# R1075X.net
KiCad netlist of a schematic drawn in EAGLE
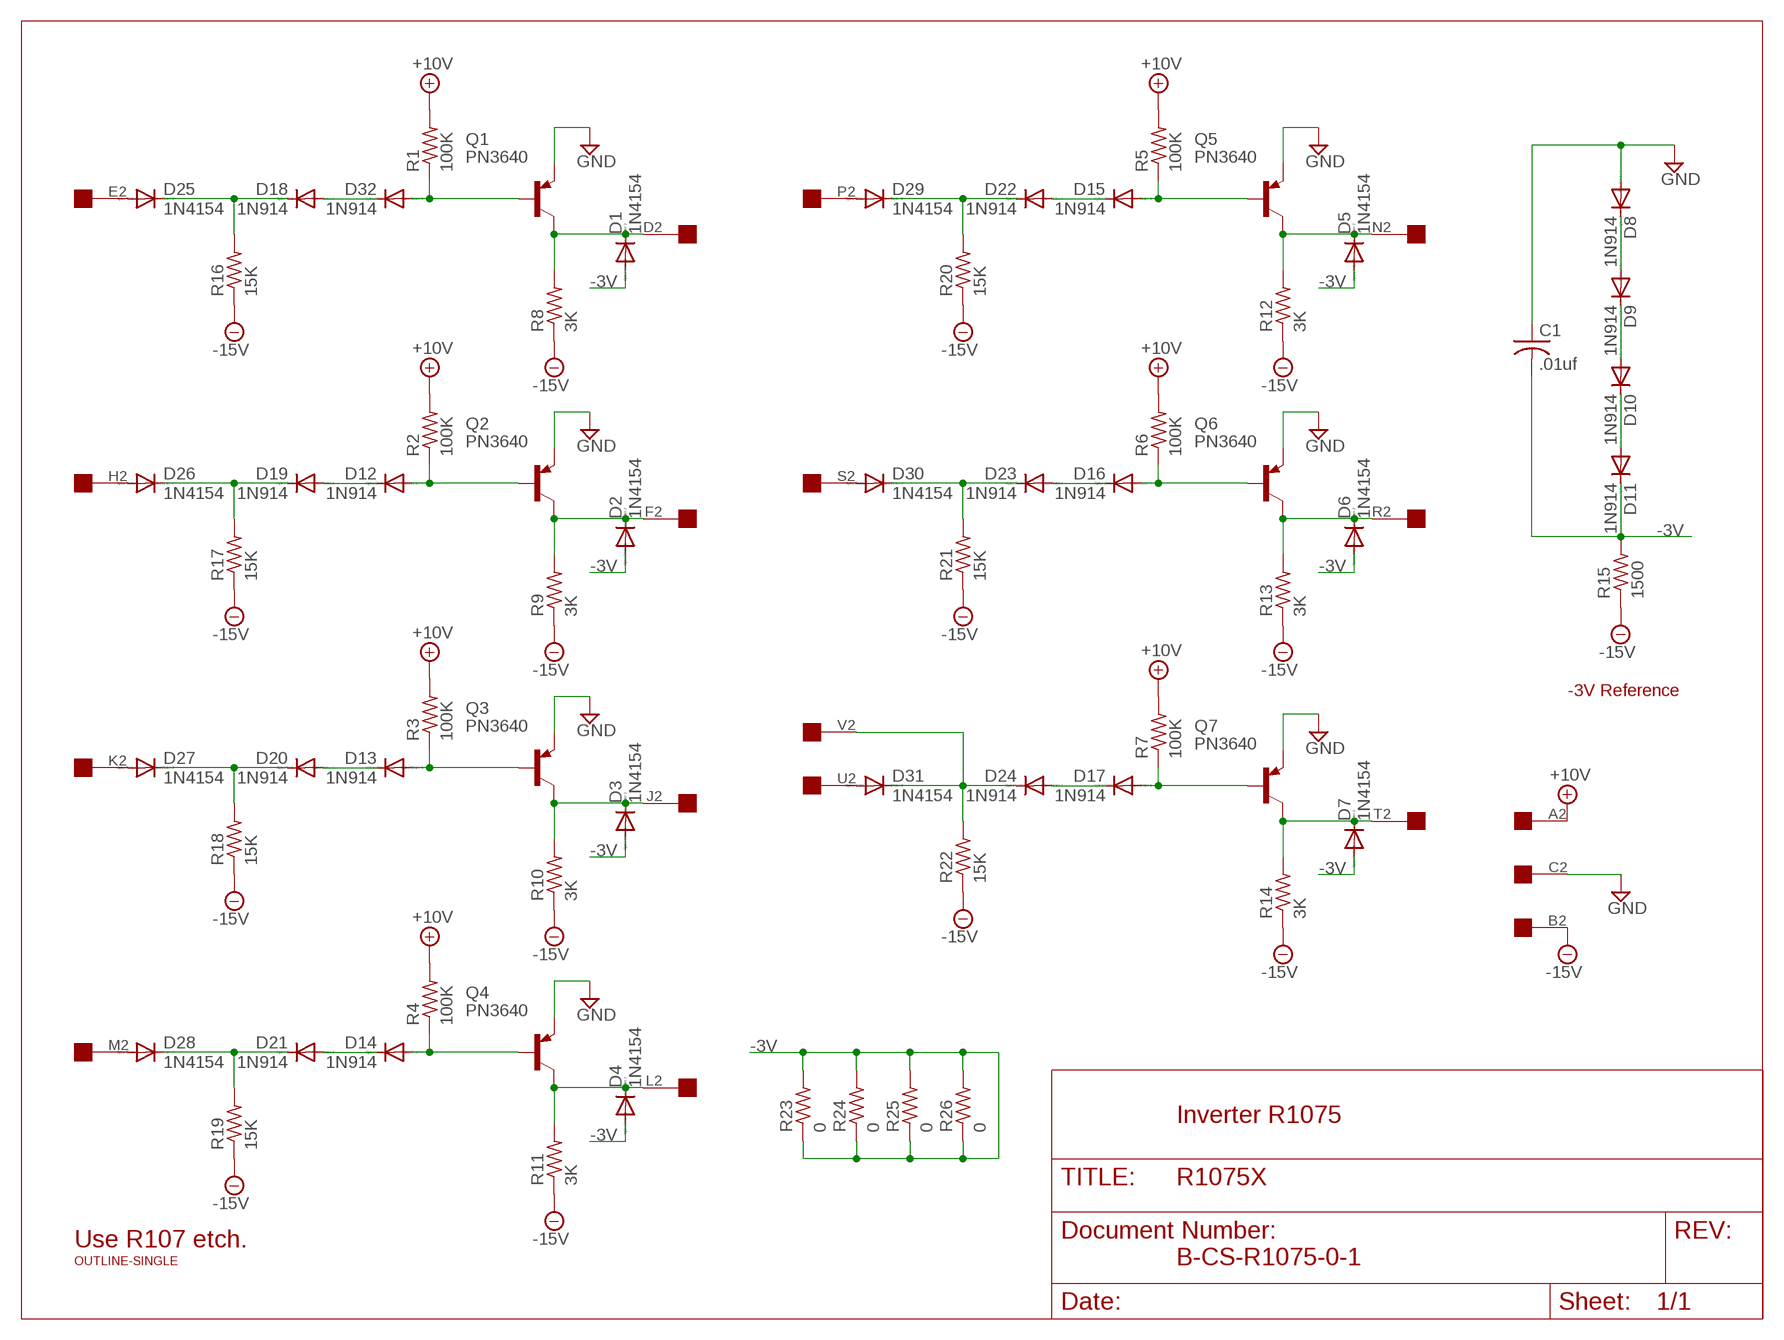
[diagram p0: schematic, sheet 1]

(export (version "E")
  (design (tool "Eeschema 10.0.6"))
  (components
    (comp (ref "C1")
      (value ".01uf")
      (footprint "eagle-import:C063-025X075")
      (libsource (lib "eagle-import") (part "C-US"))
    )
    (comp (ref "D1")
      (value "1N4154")
      (footprint "eagle-import:DO35-10")
      (libsource (lib "eagle-import") (part "1N4148DO35-10"))
    )
    (comp (ref "D2")
      (value "1N4154")
      (footprint "eagle-import:DO35-10")
      (libsource (lib "eagle-import") (part "1N4148DO35-10"))
    )
    (comp (ref "D3")
      (value "1N4154")
      (footprint "eagle-import:DO35-10")
      (libsource (lib "eagle-import") (part "1N4148DO35-10"))
    )
    (comp (ref "D4")
      (value "1N4154")
      (footprint "eagle-import:DO35-10")
      (libsource (lib "eagle-import") (part "1N4148DO35-10"))
    )
    (comp (ref "D5")
      (value "1N4154")
      (footprint "eagle-import:DO35-10")
      (libsource (lib "eagle-import") (part "1N4148DO35-10"))
    )
    (comp (ref "D6")
      (value "1N4154")
      (footprint "eagle-import:DO35-10")
      (libsource (lib "eagle-import") (part "1N4148DO35-10"))
    )
    (comp (ref "D7")
      (value "1N4154")
      (footprint "eagle-import:DO35-10")
      (libsource (lib "eagle-import") (part "1N4148DO35-10"))
    )
    (comp (ref "D8")
      (value "1N914")
      (footprint "eagle-import:DO35-10")
      (libsource (lib "eagle-import") (part "1N4148DO35-10"))
    )
    (comp (ref "D9")
      (value "1N914")
      (footprint "eagle-import:DO35-10")
      (libsource (lib "eagle-import") (part "1N4148DO35-10"))
    )
    (comp (ref "D10")
      (value "1N914")
      (footprint "eagle-import:DO35-10")
      (libsource (lib "eagle-import") (part "1N4148DO35-10"))
    )
    (comp (ref "D11")
      (value "1N914")
      (footprint "eagle-import:DO35-10")
      (libsource (lib "eagle-import") (part "1N4148DO35-10"))
    )
    (comp (ref "D12")
      (value "1N914")
      (footprint "eagle-import:DO35-10")
      (libsource (lib "eagle-import") (part "1N4148DO35-10"))
    )
    (comp (ref "D13")
      (value "1N914")
      (footprint "eagle-import:DO35-10")
      (libsource (lib "eagle-import") (part "1N4148DO35-10"))
    )
    (comp (ref "D14")
      (value "1N914")
      (footprint "eagle-import:DO35-10")
      (libsource (lib "eagle-import") (part "1N4148DO35-10"))
    )
    (comp (ref "D15")
      (value "1N914")
      (footprint "eagle-import:DO35-10")
      (libsource (lib "eagle-import") (part "1N4148DO35-10"))
    )
    (comp (ref "D16")
      (value "1N914")
      (footprint "eagle-import:DO35-10")
      (libsource (lib "eagle-import") (part "1N4148DO35-10"))
    )
    (comp (ref "D17")
      (value "1N914")
      (footprint "eagle-import:DO35-10")
      (libsource (lib "eagle-import") (part "1N4148DO35-10"))
    )
    (comp (ref "D18")
      (value "1N914")
      (footprint "eagle-import:DO35-10")
      (libsource (lib "eagle-import") (part "1N4148DO35-10"))
    )
    (comp (ref "D19")
      (value "1N914")
      (footprint "eagle-import:DO35-10")
      (libsource (lib "eagle-import") (part "1N4148DO35-10"))
    )
    (comp (ref "D20")
      (value "1N914")
      (footprint "eagle-import:DO35-10")
      (libsource (lib "eagle-import") (part "1N4148DO35-10"))
    )
    (comp (ref "D21")
      (value "1N914")
      (footprint "eagle-import:DO35-10")
      (libsource (lib "eagle-import") (part "1N4148DO35-10"))
    )
    (comp (ref "D22")
      (value "1N914")
      (footprint "eagle-import:DO35-10")
      (libsource (lib "eagle-import") (part "1N4148DO35-10"))
    )
    (comp (ref "D23")
      (value "1N914")
      (footprint "eagle-import:DO35-10")
      (libsource (lib "eagle-import") (part "1N4148DO35-10"))
    )
    (comp (ref "D24")
      (value "1N914")
      (footprint "eagle-import:DO35-10")
      (libsource (lib "eagle-import") (part "1N4148DO35-10"))
    )
    (comp (ref "D25")
      (value "1N4154")
      (footprint "eagle-import:DO35-10")
      (libsource (lib "eagle-import") (part "1N4148DO35-10"))
    )
    (comp (ref "D26")
      (value "1N4154")
      (footprint "eagle-import:DO35-10")
      (libsource (lib "eagle-import") (part "1N4148DO35-10"))
    )
    (comp (ref "D27")
      (value "1N4154")
      (footprint "eagle-import:DO35-10")
      (libsource (lib "eagle-import") (part "1N4148DO35-10"))
    )
    (comp (ref "D28")
      (value "1N4154")
      (footprint "eagle-import:DO35-10")
      (libsource (lib "eagle-import") (part "1N4148DO35-10"))
    )
    (comp (ref "D29")
      (value "1N4154")
      (footprint "eagle-import:DO35-10")
      (libsource (lib "eagle-import") (part "1N4148DO35-10"))
    )
    (comp (ref "D30")
      (value "1N4154")
      (footprint "eagle-import:DO35-10")
      (libsource (lib "eagle-import") (part "1N4148DO35-10"))
    )
    (comp (ref "D31")
      (value "1N4154")
      (footprint "eagle-import:DO35-10")
      (libsource (lib "eagle-import") (part "1N4148DO35-10"))
    )
    (comp (ref "D32")
      (value "1N914")
      (footprint "eagle-import:DO35-10")
      (libsource (lib "eagle-import") (part "1N4148DO35-10"))
    )
    (comp (ref "Q1")
      (value "PN3640")
      (footprint "eagle-import:TO39")
      (libsource (lib "eagle-import") (part "2N3637"))
    )
    (comp (ref "Q2")
      (value "PN3640")
      (footprint "eagle-import:TO39")
      (libsource (lib "eagle-import") (part "2N3637"))
    )
    (comp (ref "Q3")
      (value "PN3640")
      (footprint "eagle-import:TO39")
      (libsource (lib "eagle-import") (part "2N3637"))
    )
    (comp (ref "Q4")
      (value "PN3640")
      (footprint "eagle-import:TO39")
      (libsource (lib "eagle-import") (part "2N3637"))
    )
    (comp (ref "Q5")
      (value "PN3640")
      (footprint "eagle-import:TO39")
      (libsource (lib "eagle-import") (part "2N3637"))
    )
    (comp (ref "Q6")
      (value "PN3640")
      (footprint "eagle-import:TO39")
      (libsource (lib "eagle-import") (part "2N3637"))
    )
    (comp (ref "Q7")
      (value "PN3640")
      (footprint "eagle-import:TO39")
      (libsource (lib "eagle-import") (part "2N3637"))
    )
    (comp (ref "R1")
      (value "100K")
      (footprint "eagle-import:0207_10")
      (libsource (lib "eagle-import") (part "R-US_0207/10"))
    )
    (comp (ref "R2")
      (value "100K")
      (footprint "eagle-import:0207_10")
      (libsource (lib "eagle-import") (part "R-US_0207/10"))
    )
    (comp (ref "R3")
      (value "100K")
      (footprint "eagle-import:0207_10")
      (libsource (lib "eagle-import") (part "R-US_0207/10"))
    )
    (comp (ref "R4")
      (value "100K")
      (footprint "eagle-import:0207_10")
      (libsource (lib "eagle-import") (part "R-US_0207/10"))
    )
    (comp (ref "R5")
      (value "100K")
      (footprint "eagle-import:0207_10")
      (libsource (lib "eagle-import") (part "R-US_0207/10"))
    )
    (comp (ref "R6")
      (value "100K")
      (footprint "eagle-import:0207_10")
      (libsource (lib "eagle-import") (part "R-US_0207/10"))
    )
    (comp (ref "R7")
      (value "100K")
      (footprint "eagle-import:0207_10")
      (libsource (lib "eagle-import") (part "R-US_0207/10"))
    )
    (comp (ref "R8")
      (value "3K")
      (footprint "eagle-import:0207_10")
      (libsource (lib "eagle-import") (part "R-US_0207/10"))
    )
    (comp (ref "R9")
      (value "3K")
      (footprint "eagle-import:0207_10")
      (libsource (lib "eagle-import") (part "R-US_0207/10"))
    )
    (comp (ref "R10")
      (value "3K")
      (footprint "eagle-import:0207_10")
      (libsource (lib "eagle-import") (part "R-US_0207/10"))
    )
    (comp (ref "R11")
      (value "3K")
      (footprint "eagle-import:0207_10")
      (libsource (lib "eagle-import") (part "R-US_0207/10"))
    )
    (comp (ref "R12")
      (value "3K")
      (footprint "eagle-import:0207_10")
      (libsource (lib "eagle-import") (part "R-US_0207/10"))
    )
    (comp (ref "R13")
      (value "3K")
      (footprint "eagle-import:0207_10")
      (libsource (lib "eagle-import") (part "R-US_0207/10"))
    )
    (comp (ref "R14")
      (value "3K")
      (footprint "eagle-import:0207_10")
      (libsource (lib "eagle-import") (part "R-US_0207/10"))
    )
    (comp (ref "R15")
      (value "1500")
      (footprint "eagle-import:0207_10")
      (libsource (lib "eagle-import") (part "R-US_0207/10"))
    )
    (comp (ref "R16")
      (value "15K")
      (footprint "eagle-import:0207_10")
      (libsource (lib "eagle-import") (part "R-US_0207/10"))
    )
    (comp (ref "R17")
      (value "15K")
      (footprint "eagle-import:0207_10")
      (libsource (lib "eagle-import") (part "R-US_0207/10"))
    )
    (comp (ref "R18")
      (value "15K")
      (footprint "eagle-import:0207_10")
      (libsource (lib "eagle-import") (part "R-US_0207/10"))
    )
    (comp (ref "R19")
      (value "15K")
      (footprint "eagle-import:0207_10")
      (libsource (lib "eagle-import") (part "R-US_0207/10"))
    )
    (comp (ref "R20")
      (value "15K")
      (footprint "eagle-import:0207_10")
      (libsource (lib "eagle-import") (part "R-US_0207/10"))
    )
    (comp (ref "R21")
      (value "15K")
      (footprint "eagle-import:0207_10")
      (libsource (lib "eagle-import") (part "R-US_0207/10"))
    )
    (comp (ref "R22")
      (value "15K")
      (footprint "eagle-import:0207_10")
      (libsource (lib "eagle-import") (part "R-US_0207/10"))
    )
    (comp (ref "R23")
      (value "0")
      (footprint "eagle-import:0207_10")
      (libsource (lib "eagle-import") (part "R-US_0207/10"))
    )
    (comp (ref "R24")
      (value "0")
      (footprint "eagle-import:0207_10")
      (libsource (lib "eagle-import") (part "R-US_0207/10"))
    )
    (comp (ref "R25")
      (value "0")
      (footprint "eagle-import:0207_10")
      (libsource (lib "eagle-import") (part "R-US_0207/10"))
    )
    (comp (ref "R26")
      (value "0")
      (footprint "eagle-import:0207_10")
      (libsource (lib "eagle-import") (part "R-US_0207/10"))
    )
    (comp (ref "U$1")
      (value "OUTLINE-SINGLE")
      (footprint "eagle-import:SINGLE")
      (libsource (lib "eagle-import") (part "OUTLINE-SINGLE"))
    )
    (comp (ref "U$2")
      (value "EDGE-1")
      (footprint "eagle-import:EDGE-CON1")
      (libsource (lib "eagle-import") (part "EDGE-1"))
    )
  )
  (nets
    (net (code "1") (name "+10V") (class "Default")
      (node (ref "R1") (pin "2") (pinfunction "2_2") (pintype "passive"))
      (node (ref "R2") (pin "2") (pinfunction "2_2") (pintype "passive"))
      (node (ref "R3") (pin "2") (pinfunction "2_2") (pintype "passive"))
      (node (ref "R4") (pin "2") (pinfunction "2_2") (pintype "passive"))
      (node (ref "R5") (pin "2") (pinfunction "2_2") (pintype "passive"))
      (node (ref "R6") (pin "2") (pinfunction "2_2") (pintype "passive"))
      (node (ref "R7") (pin "2") (pinfunction "2_2") (pintype "passive"))
      (node (ref "U$2") (pin "A2") (pinfunction "1_A2") (pintype "bidirectional"))
    )
    (net (code "2") (name "-15V") (class "Default")
      (node (ref "R10") (pin "1") (pinfunction "1_1") (pintype "passive"))
      (node (ref "R11") (pin "1") (pinfunction "1_1") (pintype "passive"))
      (node (ref "R12") (pin "1") (pinfunction "1_1") (pintype "passive"))
      (node (ref "R13") (pin "1") (pinfunction "1_1") (pintype "passive"))
      (node (ref "R14") (pin "1") (pinfunction "1_1") (pintype "passive"))
      (node (ref "R15") (pin "1") (pinfunction "1_1") (pintype "passive"))
      (node (ref "R16") (pin "1") (pinfunction "1_1") (pintype "passive"))
      (node (ref "R17") (pin "1") (pinfunction "1_1") (pintype "passive"))
      (node (ref "R18") (pin "1") (pinfunction "1_1") (pintype "passive"))
      (node (ref "R19") (pin "1") (pinfunction "1_1") (pintype "passive"))
      (node (ref "R20") (pin "1") (pinfunction "1_1") (pintype "passive"))
      (node (ref "R21") (pin "1") (pinfunction "1_1") (pintype "passive"))
      (node (ref "R22") (pin "1") (pinfunction "1_1") (pintype "passive"))
      (node (ref "R8") (pin "1") (pinfunction "1_1") (pintype "passive"))
      (node (ref "R9") (pin "1") (pinfunction "1_1") (pintype "passive"))
      (node (ref "U$2") (pin "B2") (pinfunction "1_B2") (pintype "bidirectional"))
    )
    (net (code "3") (name "/-3V") (class "Default")
      (node (ref "C1") (pin "2") (pinfunction "2_2") (pintype "passive"))
      (node (ref "D1") (pin "A") (pinfunction "A_A") (pintype "passive"))
      (node (ref "D11") (pin "C") (pinfunction "C_C") (pintype "passive"))
      (node (ref "D2") (pin "A") (pinfunction "A_A") (pintype "passive"))
      (node (ref "D3") (pin "A") (pinfunction "A_A") (pintype "passive"))
      (node (ref "D4") (pin "A") (pinfunction "A_A") (pintype "passive"))
      (node (ref "D5") (pin "A") (pinfunction "A_A") (pintype "passive"))
      (node (ref "D6") (pin "A") (pinfunction "A_A") (pintype "passive"))
      (node (ref "D7") (pin "A") (pinfunction "A_A") (pintype "passive"))
      (node (ref "R15") (pin "2") (pinfunction "2_2") (pintype "passive"))
      (node (ref "R23") (pin "1") (pinfunction "1_1") (pintype "passive"))
      (node (ref "R23") (pin "2") (pinfunction "2_2") (pintype "passive"))
      (node (ref "R24") (pin "1") (pinfunction "1_1") (pintype "passive"))
      (node (ref "R24") (pin "2") (pinfunction "2_2") (pintype "passive"))
      (node (ref "R25") (pin "1") (pinfunction "1_1") (pintype "passive"))
      (node (ref "R25") (pin "2") (pinfunction "2_2") (pintype "passive"))
      (node (ref "R26") (pin "1") (pinfunction "1_1") (pintype "passive"))
      (node (ref "R26") (pin "2") (pinfunction "2_2") (pintype "passive"))
    )
    (net (code "4") (name "GND") (class "Default")
      (node (ref "C1") (pin "1") (pinfunction "1_1") (pintype "passive"))
      (node (ref "D8") (pin "A") (pinfunction "A_A") (pintype "passive"))
      (node (ref "Q1") (pin "1") (pinfunction "E_1") (pintype "passive"))
      (node (ref "Q2") (pin "1") (pinfunction "E_1") (pintype "passive"))
      (node (ref "Q3") (pin "1") (pinfunction "E_1") (pintype "passive"))
      (node (ref "Q4") (pin "1") (pinfunction "E_1") (pintype "passive"))
      (node (ref "Q5") (pin "1") (pinfunction "E_1") (pintype "passive"))
      (node (ref "Q6") (pin "1") (pinfunction "E_1") (pintype "passive"))
      (node (ref "Q7") (pin "1") (pinfunction "E_1") (pintype "passive"))
      (node (ref "U$2") (pin "C2") (pinfunction "1_C2") (pintype "bidirectional"))
    )
    (net (code "5") (name "Net-(D8-PadC)") (class "Default")
      (node (ref "D8") (pin "C") (pinfunction "C_C") (pintype "passive"))
      (node (ref "D9") (pin "A") (pinfunction "A_A") (pintype "passive"))
    )
    (net (code "6") (name "Net-(D10-PadA)") (class "Default")
      (node (ref "D10") (pin "A") (pinfunction "A_A") (pintype "passive"))
      (node (ref "D9") (pin "C") (pinfunction "C_C") (pintype "passive"))
    )
    (net (code "7") (name "Net-(D10-PadC)") (class "Default")
      (node (ref "D10") (pin "C") (pinfunction "C_C") (pintype "passive"))
      (node (ref "D11") (pin "A") (pinfunction "A_A") (pintype "passive"))
    )
    (net (code "8") (name "Net-(D12-PadC)") (class "Default")
      (node (ref "D12") (pin "C") (pinfunction "C_C") (pintype "passive"))
      (node (ref "D19") (pin "A") (pinfunction "A_A") (pintype "passive"))
    )
    (net (code "9") (name "Net-(D13-PadC)") (class "Default")
      (node (ref "D13") (pin "C") (pinfunction "C_C") (pintype "passive"))
      (node (ref "D20") (pin "A") (pinfunction "A_A") (pintype "passive"))
    )
    (net (code "10") (name "Net-(D14-PadC)") (class "Default")
      (node (ref "D14") (pin "C") (pinfunction "C_C") (pintype "passive"))
      (node (ref "D21") (pin "A") (pinfunction "A_A") (pintype "passive"))
    )
    (net (code "11") (name "Net-(D15-PadC)") (class "Default")
      (node (ref "D15") (pin "C") (pinfunction "C_C") (pintype "passive"))
      (node (ref "D22") (pin "A") (pinfunction "A_A") (pintype "passive"))
    )
    (net (code "12") (name "Net-(D16-PadC)") (class "Default")
      (node (ref "D16") (pin "C") (pinfunction "C_C") (pintype "passive"))
      (node (ref "D23") (pin "A") (pinfunction "A_A") (pintype "passive"))
    )
    (net (code "13") (name "Net-(D17-PadC)") (class "Default")
      (node (ref "D17") (pin "C") (pinfunction "C_C") (pintype "passive"))
      (node (ref "D24") (pin "A") (pinfunction "A_A") (pintype "passive"))
    )
    (net (code "14") (name "Net-(D18-PadA)") (class "Default")
      (node (ref "D18") (pin "A") (pinfunction "A_A") (pintype "passive"))
      (node (ref "D32") (pin "C") (pinfunction "C_C") (pintype "passive"))
    )
    (net (code "15") (name "Net-(D18-PadC)") (class "Default")
      (node (ref "D18") (pin "C") (pinfunction "C_C") (pintype "passive"))
      (node (ref "D25") (pin "C") (pinfunction "C_C") (pintype "passive"))
      (node (ref "R16") (pin "2") (pinfunction "2_2") (pintype "passive"))
    )
    (net (code "16") (name "Net-(D19-PadC)") (class "Default")
      (node (ref "D19") (pin "C") (pinfunction "C_C") (pintype "passive"))
      (node (ref "D26") (pin "C") (pinfunction "C_C") (pintype "passive"))
      (node (ref "R17") (pin "2") (pinfunction "2_2") (pintype "passive"))
    )
    (net (code "17") (name "Net-(D20-PadC)") (class "Default")
      (node (ref "D20") (pin "C") (pinfunction "C_C") (pintype "passive"))
      (node (ref "D27") (pin "C") (pinfunction "C_C") (pintype "passive"))
      (node (ref "R18") (pin "2") (pinfunction "2_2") (pintype "passive"))
    )
    (net (code "18") (name "Net-(D21-PadC)") (class "Default")
      (node (ref "D21") (pin "C") (pinfunction "C_C") (pintype "passive"))
      (node (ref "D28") (pin "C") (pinfunction "C_C") (pintype "passive"))
      (node (ref "R19") (pin "2") (pinfunction "2_2") (pintype "passive"))
    )
    (net (code "19") (name "Net-(D22-PadC)") (class "Default")
      (node (ref "D22") (pin "C") (pinfunction "C_C") (pintype "passive"))
      (node (ref "D29") (pin "C") (pinfunction "C_C") (pintype "passive"))
      (node (ref "R20") (pin "2") (pinfunction "2_2") (pintype "passive"))
    )
    (net (code "20") (name "Net-(D23-PadC)") (class "Default")
      (node (ref "D23") (pin "C") (pinfunction "C_C") (pintype "passive"))
      (node (ref "D30") (pin "C") (pinfunction "C_C") (pintype "passive"))
      (node (ref "R21") (pin "2") (pinfunction "2_2") (pintype "passive"))
    )
    (net (code "21") (name "Net-(Q1-B)") (class "Default")
      (node (ref "D32") (pin "A") (pinfunction "A_A") (pintype "passive"))
      (node (ref "Q1") (pin "2") (pinfunction "B_2") (pintype "passive"))
      (node (ref "R1") (pin "1") (pinfunction "1_1") (pintype "passive"))
    )
    (net (code "22") (name "Net-(Q1-C)") (class "Default")
      (node (ref "D1") (pin "C") (pinfunction "C_C") (pintype "passive"))
      (node (ref "Q1") (pin "3") (pinfunction "C_3") (pintype "passive"))
      (node (ref "R8") (pin "2") (pinfunction "2_2") (pintype "passive"))
      (node (ref "U$2") (pin "D2") (pinfunction "1_D2") (pintype "bidirectional"))
    )
    (net (code "23") (name "Net-(Q2-B)") (class "Default")
      (node (ref "D12") (pin "A") (pinfunction "A_A") (pintype "passive"))
      (node (ref "Q2") (pin "2") (pinfunction "B_2") (pintype "passive"))
      (node (ref "R2") (pin "1") (pinfunction "1_1") (pintype "passive"))
    )
    (net (code "24") (name "Net-(Q2-C)") (class "Default")
      (node (ref "D2") (pin "C") (pinfunction "C_C") (pintype "passive"))
      (node (ref "Q2") (pin "3") (pinfunction "C_3") (pintype "passive"))
      (node (ref "R9") (pin "2") (pinfunction "2_2") (pintype "passive"))
      (node (ref "U$2") (pin "F2") (pinfunction "1_F2") (pintype "bidirectional"))
    )
    (net (code "25") (name "Net-(Q3-B)") (class "Default")
      (node (ref "D13") (pin "A") (pinfunction "A_A") (pintype "passive"))
      (node (ref "Q3") (pin "2") (pinfunction "B_2") (pintype "passive"))
      (node (ref "R3") (pin "1") (pinfunction "1_1") (pintype "passive"))
    )
    (net (code "26") (name "Net-(Q3-C)") (class "Default")
      (node (ref "D3") (pin "C") (pinfunction "C_C") (pintype "passive"))
      (node (ref "Q3") (pin "3") (pinfunction "C_3") (pintype "passive"))
      (node (ref "R10") (pin "2") (pinfunction "2_2") (pintype "passive"))
      (node (ref "U$2") (pin "J2") (pinfunction "1_J2") (pintype "bidirectional"))
    )
    (net (code "27") (name "Net-(Q4-B)") (class "Default")
      (node (ref "D14") (pin "A") (pinfunction "A_A") (pintype "passive"))
      (node (ref "Q4") (pin "2") (pinfunction "B_2") (pintype "passive"))
      (node (ref "R4") (pin "1") (pinfunction "1_1") (pintype "passive"))
    )
    (net (code "28") (name "Net-(Q4-C)") (class "Default")
      (node (ref "D4") (pin "C") (pinfunction "C_C") (pintype "passive"))
      (node (ref "Q4") (pin "3") (pinfunction "C_3") (pintype "passive"))
      (node (ref "R11") (pin "2") (pinfunction "2_2") (pintype "passive"))
      (node (ref "U$2") (pin "L2") (pinfunction "1_L2") (pintype "bidirectional"))
    )
    (net (code "29") (name "Net-(Q5-B)") (class "Default")
      (node (ref "D15") (pin "A") (pinfunction "A_A") (pintype "passive"))
      (node (ref "Q5") (pin "2") (pinfunction "B_2") (pintype "passive"))
      (node (ref "R5") (pin "1") (pinfunction "1_1") (pintype "passive"))
    )
    (net (code "30") (name "Net-(Q5-C)") (class "Default")
      (node (ref "D5") (pin "C") (pinfunction "C_C") (pintype "passive"))
      (node (ref "Q5") (pin "3") (pinfunction "C_3") (pintype "passive"))
      (node (ref "R12") (pin "2") (pinfunction "2_2") (pintype "passive"))
      (node (ref "U$2") (pin "N2") (pinfunction "1_N2") (pintype "bidirectional"))
    )
    (net (code "31") (name "Net-(Q6-B)") (class "Default")
      (node (ref "D16") (pin "A") (pinfunction "A_A") (pintype "passive"))
      (node (ref "Q6") (pin "2") (pinfunction "B_2") (pintype "passive"))
      (node (ref "R6") (pin "1") (pinfunction "1_1") (pintype "passive"))
    )
    (net (code "32") (name "Net-(Q6-C)") (class "Default")
      (node (ref "D6") (pin "C") (pinfunction "C_C") (pintype "passive"))
      (node (ref "Q6") (pin "3") (pinfunction "C_3") (pintype "passive"))
      (node (ref "R13") (pin "2") (pinfunction "2_2") (pintype "passive"))
      (node (ref "U$2") (pin "R2") (pinfunction "1_R2") (pintype "bidirectional"))
    )
    (net (code "33") (name "Net-(Q7-B)") (class "Default")
      (node (ref "D17") (pin "A") (pinfunction "A_A") (pintype "passive"))
      (node (ref "Q7") (pin "2") (pinfunction "B_2") (pintype "passive"))
      (node (ref "R7") (pin "1") (pinfunction "1_1") (pintype "passive"))
    )
    (net (code "34") (name "Net-(Q7-C)") (class "Default")
      (node (ref "D7") (pin "C") (pinfunction "C_C") (pintype "passive"))
      (node (ref "Q7") (pin "3") (pinfunction "C_3") (pintype "passive"))
      (node (ref "R14") (pin "2") (pinfunction "2_2") (pintype "passive"))
      (node (ref "U$2") (pin "T2") (pinfunction "1_T2") (pintype "bidirectional"))
    )
    (net (code "35") (name "Net-(U$2E-1)") (class "Default")
      (node (ref "D25") (pin "A") (pinfunction "A_A") (pintype "passive"))
      (node (ref "U$2") (pin "E2") (pinfunction "1_E2") (pintype "bidirectional"))
    )
    (net (code "36") (name "Net-(U$2G-1)") (class "Default")
      (node (ref "D26") (pin "A") (pinfunction "A_A") (pintype "passive"))
      (node (ref "U$2") (pin "H2") (pinfunction "1_H2") (pintype "bidirectional"))
    )
    (net (code "37") (name "Net-(U$2I-1)") (class "Default")
      (node (ref "D27") (pin "A") (pinfunction "A_A") (pintype "passive"))
      (node (ref "U$2") (pin "K2") (pinfunction "1_K2") (pintype "bidirectional"))
    )
    (net (code "38") (name "Net-(U$2K-1)") (class "Default")
      (node (ref "D28") (pin "A") (pinfunction "A_A") (pintype "passive"))
      (node (ref "U$2") (pin "M2") (pinfunction "1_M2") (pintype "bidirectional"))
    )
    (net (code "39") (name "Net-(U$2M-1)") (class "Default")
      (node (ref "D29") (pin "A") (pinfunction "A_A") (pintype "passive"))
      (node (ref "U$2") (pin "P2") (pinfunction "1_P2") (pintype "bidirectional"))
    )
    (net (code "40") (name "Net-(U$2O-1)") (class "Default")
      (node (ref "D30") (pin "A") (pinfunction "A_A") (pintype "passive"))
      (node (ref "U$2") (pin "S2") (pinfunction "1_S2") (pintype "bidirectional"))
    )
    (net (code "41") (name "Net-(U$2Q-1)") (class "Default")
      (node (ref "D31") (pin "A") (pinfunction "A_A") (pintype "passive"))
      (node (ref "U$2") (pin "U2") (pinfunction "1_U2") (pintype "bidirectional"))
    )
    (net (code "42") (name "Net-(U$2R-1)") (class "Default")
      (node (ref "D24") (pin "C") (pinfunction "C_C") (pintype "passive"))
      (node (ref "D31") (pin "C") (pinfunction "C_C") (pintype "passive"))
      (node (ref "R22") (pin "2") (pinfunction "2_2") (pintype "passive"))
      (node (ref "U$2") (pin "V2") (pinfunction "1_V2") (pintype "bidirectional"))
    )
  )
)
